# Commodore_KB_Tester.net
KiCad netlist of a schematic drawn in EAGLE
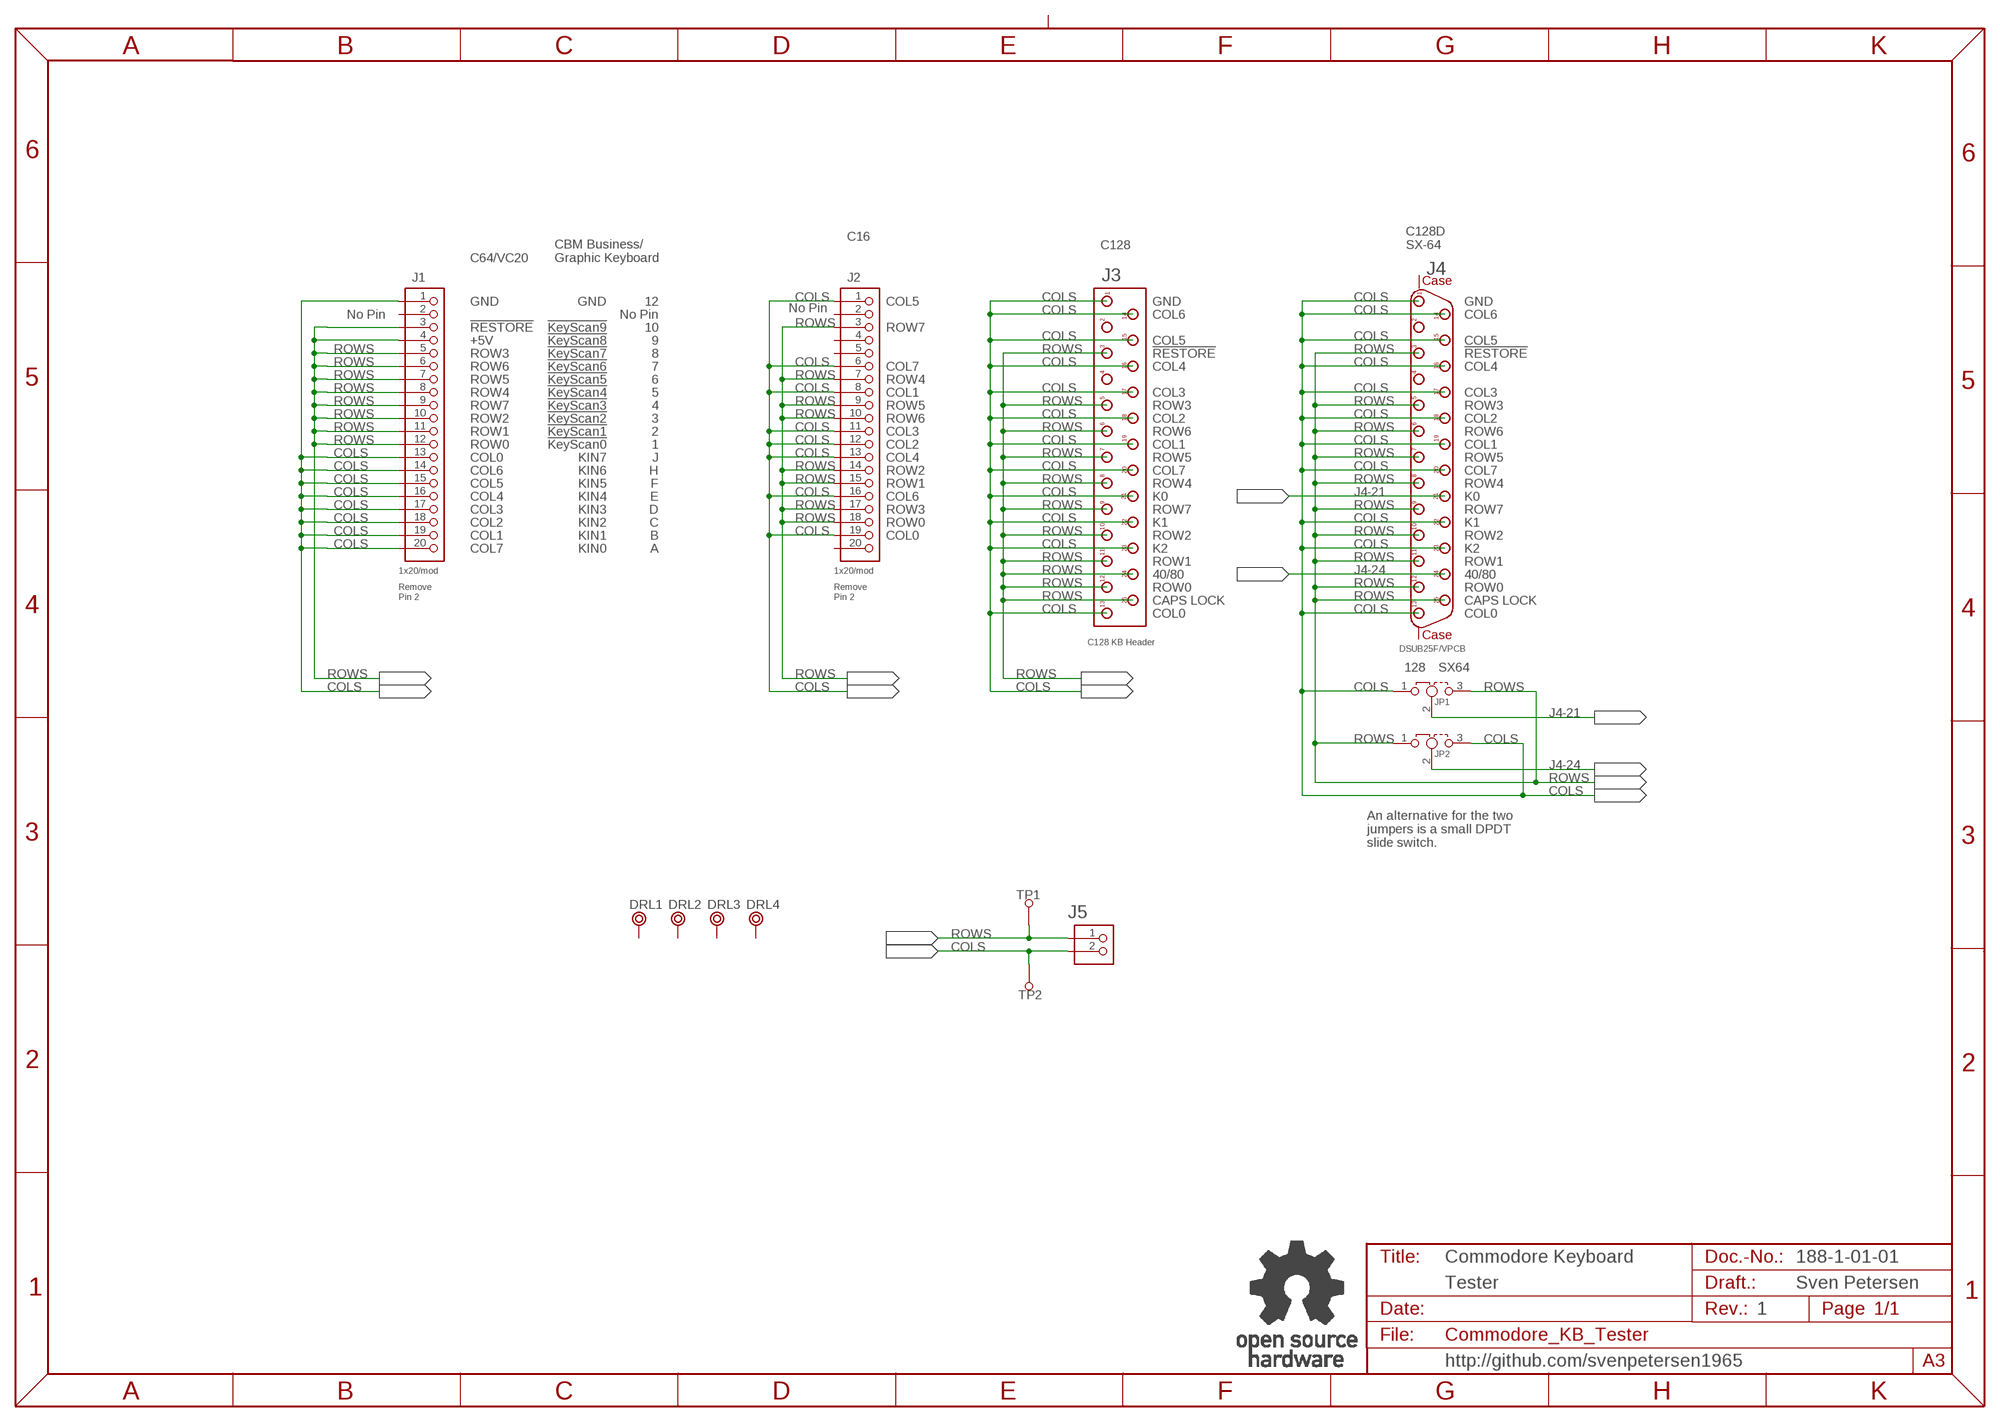
[diagram p0: schematic, sheet 1]

(export (version "E")
  (design (tool "Eeschema 10.0.6"))
  (components
    (comp (ref "DRL1")
      (value "BOHR3,5")
      (footprint "eagle-import:BOHR3,5")
      (libsource (lib "eagle-import") (part "BOHR3,5"))
    )
    (comp (ref "DRL2")
      (value "BOHR3,5")
      (footprint "eagle-import:BOHR3,5")
      (libsource (lib "eagle-import") (part "BOHR3,5"))
    )
    (comp (ref "DRL3")
      (value "BOHR3,5")
      (footprint "eagle-import:BOHR3,5")
      (libsource (lib "eagle-import") (part "BOHR3,5"))
    )
    (comp (ref "DRL4")
      (value "BOHR3,5")
      (footprint "eagle-import:BOHR3,5")
      (libsource (lib "eagle-import") (part "BOHR3,5"))
    )
    (comp (ref "J1")
      (value "1x20/mod")
      (footprint "eagle-import:1X20")
      (libsource (lib "eagle-import") (part "PINHD-1X20"))
    )
    (comp (ref "J2")
      (value "1x20/mod")
      (footprint "eagle-import:1X20")
      (libsource (lib "eagle-import") (part "PINHD-1X20"))
    )
    (comp (ref "J3")
      (value "C128 KB Header")
      (footprint "eagle-import:C128KB_HEADER")
      (libsource (lib "eagle-import") (part "C128_KBHEADER"))
    )
    (comp (ref "J4")
      (value "DSUB25F/VPCB")
      (footprint "eagle-import:DS25F-V")
      (libsource (lib "eagle-import") (part "DS25F-V-CL"))
    )
    (comp (ref "J5")
      (value "PINHD-1X2")
      (footprint "eagle-import:1X02")
      (libsource (lib "eagle-import") (part "PINHD-1X2"))
    )
    (comp (ref "JP1")
      (value "DJUMPER")
      (footprint "eagle-import:1X03")
      (libsource (lib "eagle-import") (part "DJUMPER"))
    )
    (comp (ref "JP2")
      (value "DJUMPER")
      (footprint "eagle-import:1X03")
      (libsource (lib "eagle-import") (part "DJUMPER"))
    )
    (comp (ref "TP1")
      (value "1,3/2,0")
      (footprint "eagle-import:1,3_2,0")
      (libsource (lib "eagle-import") (part "1,3/2,0"))
    )
    (comp (ref "TP2")
      (value "1,3/2,0")
      (footprint "eagle-import:1,3_2,0")
      (libsource (lib "eagle-import") (part "1,3/2,0"))
    )
    (comp (ref "U$12")
      (value "OPEN_SOURCE_HW")
      (footprint "eagle-import:OPENHW")
      (libsource (lib "eagle-import") (part "OPEN_SOURCE_HW"))
    )
  )
  (nets
    (net (code "1") (name "/COLS") (class "Default")
      (node (ref "J1") (pin "1") (pinfunction "1_1") (pintype "passive"))
      (node (ref "J1") (pin "13") (pinfunction "13_13") (pintype "passive"))
      (node (ref "J1") (pin "14") (pinfunction "14_14") (pintype "passive"))
      (node (ref "J1") (pin "15") (pinfunction "15_15") (pintype "passive"))
      (node (ref "J1") (pin "16") (pinfunction "16_16") (pintype "passive"))
      (node (ref "J1") (pin "17") (pinfunction "17_17") (pintype "passive"))
      (node (ref "J1") (pin "18") (pinfunction "18_18") (pintype "passive"))
      (node (ref "J1") (pin "19") (pinfunction "19_19") (pintype "passive"))
      (node (ref "J1") (pin "20") (pinfunction "20_20") (pintype "passive"))
      (node (ref "J2") (pin "1") (pinfunction "1_1") (pintype "passive"))
      (node (ref "J2") (pin "11") (pinfunction "11_11") (pintype "passive"))
      (node (ref "J2") (pin "12") (pinfunction "12_12") (pintype "passive"))
      (node (ref "J2") (pin "13") (pinfunction "13_13") (pintype "passive"))
      (node (ref "J2") (pin "16") (pinfunction "16_16") (pintype "passive"))
      (node (ref "J2") (pin "19") (pinfunction "19_19") (pintype "passive"))
      (node (ref "J2") (pin "6") (pinfunction "6_6") (pintype "passive"))
      (node (ref "J2") (pin "8") (pinfunction "8_8") (pintype "passive"))
      (node (ref "J3") (pin "1") (pinfunction "1_1") (pintype "passive"))
      (node (ref "J3") (pin "13") (pinfunction "13_13") (pintype "passive"))
      (node (ref "J3") (pin "14") (pinfunction "14_14") (pintype "passive"))
      (node (ref "J3") (pin "15") (pinfunction "15_15") (pintype "passive"))
      (node (ref "J3") (pin "16") (pinfunction "16_16") (pintype "passive"))
      (node (ref "J3") (pin "17") (pinfunction "17_17") (pintype "passive"))
      (node (ref "J3") (pin "18") (pinfunction "18_18") (pintype "passive"))
      (node (ref "J3") (pin "19") (pinfunction "19_19") (pintype "passive"))
      (node (ref "J3") (pin "20") (pinfunction "20_20") (pintype "passive"))
      (node (ref "J3") (pin "21") (pinfunction "21_21") (pintype "passive"))
      (node (ref "J3") (pin "22") (pinfunction "22_22") (pintype "passive"))
      (node (ref "J3") (pin "23") (pinfunction "23_23") (pintype "passive"))
      (node (ref "J4") (pin "1") (pinfunction "1_1") (pintype "passive"))
      (node (ref "J4") (pin "13") (pinfunction "13_13") (pintype "passive"))
      (node (ref "J4") (pin "14") (pinfunction "14_14") (pintype "passive"))
      (node (ref "J4") (pin "15") (pinfunction "15_15") (pintype "passive"))
      (node (ref "J4") (pin "16") (pinfunction "16_16") (pintype "passive"))
      (node (ref "J4") (pin "17") (pinfunction "17_17") (pintype "passive"))
      (node (ref "J4") (pin "18") (pinfunction "18_18") (pintype "passive"))
      (node (ref "J4") (pin "19") (pinfunction "19_19") (pintype "passive"))
      (node (ref "J4") (pin "20") (pinfunction "20_20") (pintype "passive"))
      (node (ref "J4") (pin "22") (pinfunction "22_22") (pintype "passive"))
      (node (ref "J4") (pin "23") (pinfunction "23_23") (pintype "passive"))
      (node (ref "J5") (pin "2") (pinfunction "2_2") (pintype "passive"))
      (node (ref "JP1") (pin "1") (pinfunction "1_1") (pintype "bidirectional"))
      (node (ref "JP2") (pin "3") (pinfunction "3_3") (pintype "bidirectional"))
      (node (ref "TP2") (pin "1") (pinfunction "1_1") (pintype "passive"))
    )
    (net (code "2") (name "/J4-21") (class "Default")
      (node (ref "J4") (pin "21") (pinfunction "21_21") (pintype "passive"))
      (node (ref "JP1") (pin "2") (pinfunction "2_2") (pintype "bidirectional"))
    )
    (net (code "3") (name "/J4-24") (class "Default")
      (node (ref "J4") (pin "24") (pinfunction "24_24") (pintype "passive"))
      (node (ref "JP2") (pin "2") (pinfunction "2_2") (pintype "bidirectional"))
    )
    (net (code "4") (name "/ROWS") (class "Default")
      (node (ref "J1") (pin "10") (pinfunction "10_10") (pintype "passive"))
      (node (ref "J1") (pin "11") (pinfunction "11_11") (pintype "passive"))
      (node (ref "J1") (pin "12") (pinfunction "12_12") (pintype "passive"))
      (node (ref "J1") (pin "3") (pinfunction "3_3") (pintype "passive"))
      (node (ref "J1") (pin "4") (pinfunction "4_4") (pintype "passive"))
      (node (ref "J1") (pin "5") (pinfunction "5_5") (pintype "passive"))
      (node (ref "J1") (pin "6") (pinfunction "6_6") (pintype "passive"))
      (node (ref "J1") (pin "7") (pinfunction "7_7") (pintype "passive"))
      (node (ref "J1") (pin "8") (pinfunction "8_8") (pintype "passive"))
      (node (ref "J1") (pin "9") (pinfunction "9_9") (pintype "passive"))
      (node (ref "J2") (pin "10") (pinfunction "10_10") (pintype "passive"))
      (node (ref "J2") (pin "14") (pinfunction "14_14") (pintype "passive"))
      (node (ref "J2") (pin "15") (pinfunction "15_15") (pintype "passive"))
      (node (ref "J2") (pin "17") (pinfunction "17_17") (pintype "passive"))
      (node (ref "J2") (pin "18") (pinfunction "18_18") (pintype "passive"))
      (node (ref "J2") (pin "3") (pinfunction "3_3") (pintype "passive"))
      (node (ref "J2") (pin "7") (pinfunction "7_7") (pintype "passive"))
      (node (ref "J2") (pin "9") (pinfunction "9_9") (pintype "passive"))
      (node (ref "J3") (pin "10") (pinfunction "10_10") (pintype "passive"))
      (node (ref "J3") (pin "11") (pinfunction "11_11") (pintype "passive"))
      (node (ref "J3") (pin "12") (pinfunction "12_12") (pintype "passive"))
      (node (ref "J3") (pin "24") (pinfunction "24_24") (pintype "passive"))
      (node (ref "J3") (pin "25") (pinfunction "25_25") (pintype "passive"))
      (node (ref "J3") (pin "3") (pinfunction "3_3") (pintype "passive"))
      (node (ref "J3") (pin "5") (pinfunction "5_5") (pintype "passive"))
      (node (ref "J3") (pin "6") (pinfunction "6_6") (pintype "passive"))
      (node (ref "J3") (pin "7") (pinfunction "7_7") (pintype "passive"))
      (node (ref "J3") (pin "8") (pinfunction "8_8") (pintype "passive"))
      (node (ref "J3") (pin "9") (pinfunction "9_9") (pintype "passive"))
      (node (ref "J4") (pin "10") (pinfunction "10_10") (pintype "passive"))
      (node (ref "J4") (pin "11") (pinfunction "11_11") (pintype "passive"))
      (node (ref "J4") (pin "12") (pinfunction "12_12") (pintype "passive"))
      (node (ref "J4") (pin "25") (pinfunction "25_25") (pintype "passive"))
      (node (ref "J4") (pin "3") (pinfunction "3_3") (pintype "passive"))
      (node (ref "J4") (pin "5") (pinfunction "5_5") (pintype "passive"))
      (node (ref "J4") (pin "6") (pinfunction "6_6") (pintype "passive"))
      (node (ref "J4") (pin "7") (pinfunction "7_7") (pintype "passive"))
      (node (ref "J4") (pin "8") (pinfunction "8_8") (pintype "passive"))
      (node (ref "J4") (pin "9") (pinfunction "9_9") (pintype "passive"))
      (node (ref "J5") (pin "1") (pinfunction "1_1") (pintype "passive"))
      (node (ref "JP1") (pin "3") (pinfunction "3_3") (pintype "bidirectional"))
      (node (ref "JP2") (pin "1") (pinfunction "1_1") (pintype "bidirectional"))
      (node (ref "TP1") (pin "1") (pinfunction "1_1") (pintype "passive"))
    )
    (net (code "5") (name "unconnected-(DRL1-PadP$1)") (class "Default")
      (node (ref "DRL1") (pin "P$1") (pinfunction "P$1_P$1") (pintype "passive"))
    )
    (net (code "6") (name "unconnected-(DRL2-PadP$1)") (class "Default")
      (node (ref "DRL2") (pin "P$1") (pinfunction "P$1_P$1") (pintype "passive"))
    )
    (net (code "7") (name "unconnected-(DRL3-PadP$1)") (class "Default")
      (node (ref "DRL3") (pin "P$1") (pinfunction "P$1_P$1") (pintype "passive"))
    )
    (net (code "8") (name "unconnected-(DRL4-PadP$1)") (class "Default")
      (node (ref "DRL4") (pin "P$1") (pinfunction "P$1_P$1") (pintype "passive"))
    )
    (net (code "9") (name "unconnected-(J1-Pad2)") (class "Default")
      (node (ref "J1") (pin "2") (pinfunction "2_2") (pintype "passive"))
    )
    (net (code "10") (name "unconnected-(J2-Pad2)") (class "Default")
      (node (ref "J2") (pin "2") (pinfunction "2_2") (pintype "passive"))
    )
    (net (code "11") (name "unconnected-(J2-Pad4)") (class "Default")
      (node (ref "J2") (pin "4") (pinfunction "4_4") (pintype "passive"))
    )
    (net (code "12") (name "unconnected-(J2-Pad5)") (class "Default")
      (node (ref "J2") (pin "5") (pinfunction "5_5") (pintype "passive"))
    )
    (net (code "13") (name "unconnected-(J2-Pad20)") (class "Default")
      (node (ref "J2") (pin "20") (pinfunction "20_20") (pintype "passive"))
    )
    (net (code "14") (name "unconnected-(J3-Pad2)") (class "Default")
      (node (ref "J3") (pin "2") (pinfunction "2_2") (pintype "passive"))
    )
    (net (code "15") (name "unconnected-(J3-Pad4)") (class "Default")
      (node (ref "J3") (pin "4") (pinfunction "4_4") (pintype "passive"))
    )
    (net (code "16") (name "unconnected-(J4-CL1-PadPE1)") (class "Default")
      (node (ref "J4") (pin "PE1") (pinfunction "CL1_PE1") (pintype "bidirectional"))
    )
    (net (code "17") (name "unconnected-(J4-CL2-PadPE2)") (class "Default")
      (node (ref "J4") (pin "PE2") (pinfunction "CL2_PE2") (pintype "bidirectional"))
    )
    (net (code "18") (name "unconnected-(J4-Pad2)") (class "Default")
      (node (ref "J4") (pin "2") (pinfunction "2_2") (pintype "passive"))
    )
    (net (code "19") (name "unconnected-(J4-Pad4)") (class "Default")
      (node (ref "J4") (pin "4") (pinfunction "4_4") (pintype "passive"))
    )
  )
)
